# LCDTFT_FPC40P_SPI4_4p0INCH_RTP.net
KiCad netlist of a schematic drawn in Altium Designer
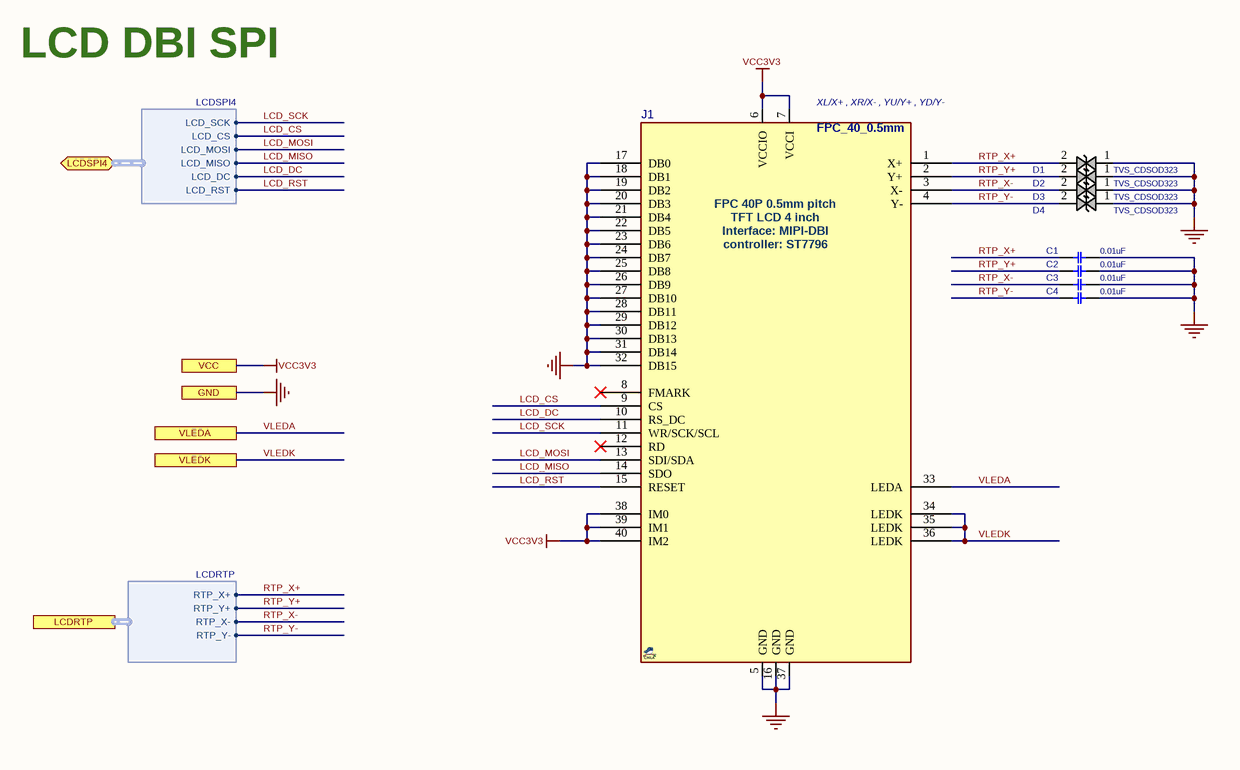
[diagram p0: LCDTFT_FPC40P_SPI4_4p0INCH_RTP.SchDoc]

(export (version "E")
  (design (tool "Eeschema 10.0.6"))
  (components
    (comp (ref "C1")
      (value "0.01uF")
      (footprint "C0402")
      (description "CAP, MLCC")
      (libsource (lib "passive_smd") (part "CAP_SMD_MLCC"))
    )
    (comp (ref "C2")
      (value "0.01uF")
      (footprint "C0402")
      (description "CAP, MLCC")
      (libsource (lib "passive_smd") (part "CAP_SMD_MLCC"))
    )
    (comp (ref "C3")
      (value "0.01uF")
      (footprint "C0402")
      (description "CAP, MLCC")
      (libsource (lib "passive_smd") (part "CAP_SMD_MLCC"))
    )
    (comp (ref "C4")
      (value "0.01uF")
      (footprint "C0402")
      (description "CAP, MLCC")
      (libsource (lib "passive_smd") (part "CAP_SMD_MLCC"))
    )
    (comp (ref "D1")
      (value "TVS_CDSOD323")
      (footprint "D0805")
      (description "TVS, ESD PROTECT, Bidirectional")
      (fields (field (name "MANF_P#") "CDSOD323-T12C") (field (name "MANF") "Bourns"))
      (libsource (lib "protect_tvs_esd_fuse") (part "TVS_CDSOD323"))
    )
    (comp (ref "D2")
      (value "TVS_CDSOD323")
      (footprint "D0805")
      (description "TVS, ESD PROTECT, Bidirectional")
      (fields (field (name "MANF_P#") "CDSOD323-T12C") (field (name "MANF") "Bourns"))
      (libsource (lib "protect_tvs_esd_fuse") (part "TVS_CDSOD323"))
    )
    (comp (ref "D3")
      (value "TVS_CDSOD323")
      (footprint "D0805")
      (description "TVS, ESD PROTECT, Bidirectional")
      (fields (field (name "MANF_P#") "CDSOD323-T12C") (field (name "MANF") "Bourns"))
      (libsource (lib "protect_tvs_esd_fuse") (part "TVS_CDSOD323"))
    )
    (comp (ref "D4")
      (value "TVS_CDSOD323")
      (footprint "D0805")
      (description "TVS, ESD PROTECT, Bidirectional")
      (fields (field (name "MANF_P#") "CDSOD323-T12C") (field (name "MANF") "Bourns"))
      (libsource (lib "protect_tvs_esd_fuse") (part "TVS_CDSOD323"))
    )
    (comp (ref "J1")
      (value "FPC50_40")
      (footprint "FPC50_40T")
      (description "LCD TFT Color, FPC40P, 4\" with touch")
      (fields (field (name "MANF") "Hirose") (field (name "MANF_P#") "FH12A-40S-0.5SH"))
      (libsource (lib "lcdtft") (part "LCDTFT_DBI_FPC40P_4INCH"))
    )
  )
  (nets
    (net (code "3") (name "/LCD_CS") (class "Default")
      (node (ref "J1") (pin "9") (pinfunction "CS_9") (pintype "passive"))
    )
    (net (code "4") (name "/LCD_DC") (class "Default")
      (node (ref "J1") (pin "10") (pinfunction "RS_DC_10") (pintype "passive"))
    )
    (net (code "5") (name "/LCD_MISO") (class "Default")
      (node (ref "J1") (pin "14") (pinfunction "SDO_14") (pintype "passive"))
    )
    (net (code "6") (name "/LCD_MOSI") (class "Default")
      (node (ref "J1") (pin "13") (pinfunction "SDI/SDA_13") (pintype "passive"))
    )
    (net (code "7") (name "/LCD_RST") (class "Default")
      (node (ref "J1") (pin "15") (pinfunction "RESET_15") (pintype "passive"))
    )
    (net (code "8") (name "/LCD_SCK") (class "Default")
      (node (ref "J1") (pin "11") (pinfunction "WR/SCK/SCL_11") (pintype "passive"))
    )
    (net (code "9") (name "/RTP_X+") (class "Default")
      (node (ref "C1") (pin "2") (pinfunction "2_2") (pintype "passive"))
      (node (ref "D1") (pin "2") (pinfunction "2_2") (pintype "passive"))
      (node (ref "J1") (pin "1") (pinfunction "X+_1") (pintype "passive"))
    )
    (net (code "10") (name "/RTP_X-") (class "Default")
      (node (ref "C3") (pin "2") (pinfunction "2_2") (pintype "passive"))
      (node (ref "D3") (pin "2") (pinfunction "2_2") (pintype "passive"))
      (node (ref "J1") (pin "3") (pinfunction "X-_3") (pintype "passive"))
    )
    (net (code "11") (name "/RTP_Y+") (class "Default")
      (node (ref "C2") (pin "2") (pinfunction "2_2") (pintype "passive"))
      (node (ref "D2") (pin "2") (pinfunction "2_2") (pintype "passive"))
      (node (ref "J1") (pin "2") (pinfunction "Y+_2") (pintype "passive"))
    )
    (net (code "12") (name "/RTP_Y-") (class "Default")
      (node (ref "C4") (pin "2") (pinfunction "2_2") (pintype "passive"))
      (node (ref "D4") (pin "2") (pinfunction "2_2") (pintype "passive"))
      (node (ref "J1") (pin "4") (pinfunction "Y-_4") (pintype "passive"))
    )
    (net (code "13") (name "/VLEDA") (class "Default")
      (node (ref "J1") (pin "33") (pinfunction "LEDA_33") (pintype "passive"))
    )
    (net (code "14") (name "/VLEDK") (class "Default")
      (node (ref "J1") (pin "34") (pinfunction "LEDK_34") (pintype "passive"))
      (node (ref "J1") (pin "35") (pinfunction "LEDK_35") (pintype "passive"))
      (node (ref "J1") (pin "36") (pinfunction "LEDK_36") (pintype "passive"))
    )
    (net (code "17") (name "GND") (class "Default")
      (node (ref "C1") (pin "1") (pinfunction "1_1") (pintype "passive"))
      (node (ref "C2") (pin "1") (pinfunction "1_1") (pintype "passive"))
      (node (ref "C3") (pin "1") (pinfunction "1_1") (pintype "passive"))
      (node (ref "C4") (pin "1") (pinfunction "1_1") (pintype "passive"))
      (node (ref "D1") (pin "1") (pinfunction "1_1") (pintype "passive"))
      (node (ref "D2") (pin "1") (pinfunction "1_1") (pintype "passive"))
      (node (ref "D3") (pin "1") (pinfunction "1_1") (pintype "passive"))
      (node (ref "D4") (pin "1") (pinfunction "1_1") (pintype "passive"))
      (node (ref "J1") (pin "16") (pinfunction "GND_16") (pintype "passive"))
      (node (ref "J1") (pin "17") (pinfunction "DB0_17") (pintype "passive"))
      (node (ref "J1") (pin "18") (pinfunction "DB1_18") (pintype "passive"))
      (node (ref "J1") (pin "19") (pinfunction "DB2_19") (pintype "passive"))
      (node (ref "J1") (pin "20") (pinfunction "DB3_20") (pintype "passive"))
      (node (ref "J1") (pin "21") (pinfunction "DB4_21") (pintype "passive"))
      (node (ref "J1") (pin "22") (pinfunction "DB5_22") (pintype "passive"))
      (node (ref "J1") (pin "23") (pinfunction "DB6_23") (pintype "passive"))
      (node (ref "J1") (pin "24") (pinfunction "DB7_24") (pintype "passive"))
      (node (ref "J1") (pin "25") (pinfunction "DB8_25") (pintype "passive"))
      (node (ref "J1") (pin "26") (pinfunction "DB9_26") (pintype "passive"))
      (node (ref "J1") (pin "27") (pinfunction "DB10_27") (pintype "passive"))
      (node (ref "J1") (pin "28") (pinfunction "DB11_28") (pintype "passive"))
      (node (ref "J1") (pin "29") (pinfunction "DB12_29") (pintype "passive"))
      (node (ref "J1") (pin "30") (pinfunction "DB13_30") (pintype "passive"))
      (node (ref "J1") (pin "31") (pinfunction "DB14_31") (pintype "passive"))
      (node (ref "J1") (pin "32") (pinfunction "DB15_32") (pintype "passive"))
      (node (ref "J1") (pin "37") (pinfunction "GND_37") (pintype "passive"))
      (node (ref "J1") (pin "5") (pinfunction "GND_5") (pintype "passive"))
    )
    (net (code "18") (name "VCC3V3") (class "Default")
      (node (ref "J1") (pin "38") (pinfunction "IM0_38") (pintype "passive"))
      (node (ref "J1") (pin "39") (pinfunction "IM1_39") (pintype "passive"))
      (node (ref "J1") (pin "40") (pinfunction "IM2_40") (pintype "passive"))
      (node (ref "J1") (pin "6") (pinfunction "VCCIO_6") (pintype "passive"))
      (node (ref "J1") (pin "7") (pinfunction "VCCI_7") (pintype "passive"))
    )
    (net (code "19") (name "unconnected-(J1-FMARK-Pad8)") (class "Default")
      (node (ref "J1") (pin "8") (pinfunction "FMARK_8") (pintype "passive+no_connect"))
    )
    (net (code "20") (name "unconnected-(J1-RD-Pad12)") (class "Default")
      (node (ref "J1") (pin "12") (pinfunction "RD_12") (pintype "passive+no_connect"))
    )
  )
)
